# untitled.net
KiCad netlist of a schematic drawn in EAGLE
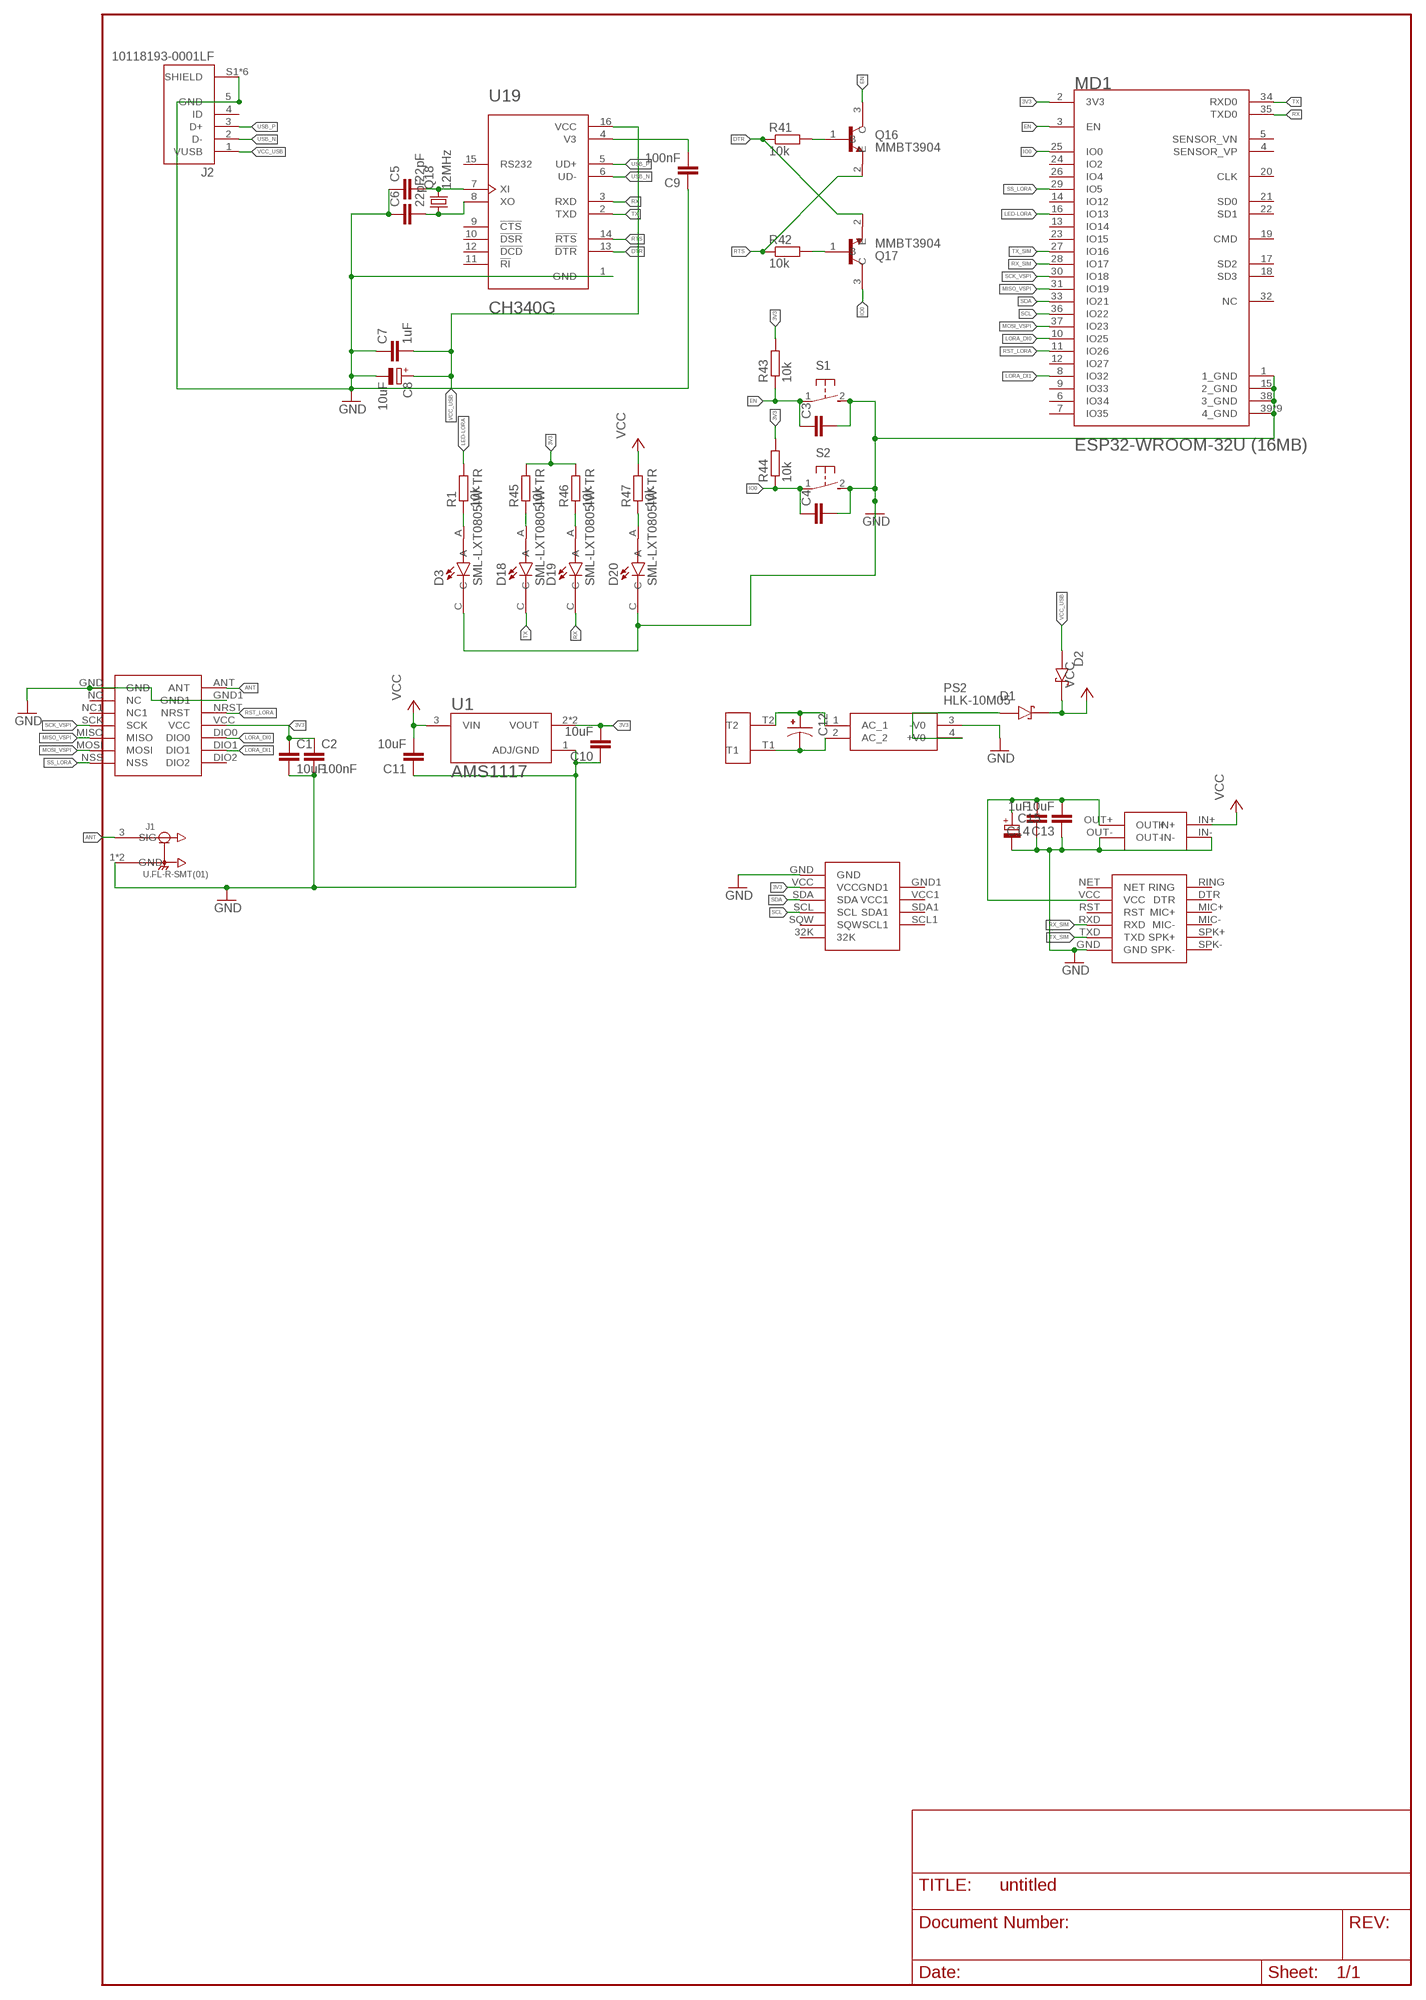
[diagram p0: schematic, sheet 1]

(export (version "E")
  (design (tool "Eeschema 10.0.6"))
  (components
    (comp (ref "C1")
      (value "10uF")
      (footprint "eagle-import:C0805K")
      (libsource (lib "eagle-import") (part "C-EUC0805K"))
    )
    (comp (ref "C2")
      (value "100nF")
      (footprint "eagle-import:C0805K")
      (libsource (lib "eagle-import") (part "C-EUC0805K"))
    )
    (comp (ref "C3")
      (value "C-EUC0805K")
      (footprint "eagle-import:C0805K")
      (libsource (lib "eagle-import") (part "C-EUC0805K"))
    )
    (comp (ref "C4")
      (value "C-EUC0805K")
      (footprint "eagle-import:C0805K")
      (libsource (lib "eagle-import") (part "C-EUC0805K"))
    )
    (comp (ref "C5")
      (value "22pF")
      (footprint "eagle-import:C0805K")
      (libsource (lib "eagle-import") (part "C-EUC0805K"))
    )
    (comp (ref "C6")
      (value "22pF")
      (footprint "eagle-import:C0805K")
      (libsource (lib "eagle-import") (part "C-EUC0805K"))
    )
    (comp (ref "C7")
      (value "1uF")
      (footprint "eagle-import:C0805K")
      (libsource (lib "eagle-import") (part "C-EUC0805K"))
    )
    (comp (ref "C8")
      (value "10uF")
      (footprint "eagle-import:153CLV-0505")
      (libsource (lib "eagle-import") (part "CPOL-EU153CLV-0505"))
    )
    (comp (ref "C9")
      (value "100nF")
      (footprint "eagle-import:C0805K")
      (libsource (lib "eagle-import") (part "C-EUC0805K"))
    )
    (comp (ref "C10")
      (value "10uF")
      (footprint "eagle-import:C0805K")
      (libsource (lib "eagle-import") (part "C-EUC0805K"))
    )
    (comp (ref "C11")
      (value "10uF")
      (footprint "eagle-import:C0805K")
      (libsource (lib "eagle-import") (part "C-EUC0805K"))
    )
    (comp (ref "C12")
      (value "UPM2E100MHD1TO")
      (footprint "eagle-import:CAPPRD500W60D1250H2200")
      (fields (field (name "MF") "Nichicon"))
      (libsource (lib "eagle-import") (part "UPM2E100MHD1TO"))
    )
    (comp (ref "C13")
      (value "10uF")
      (footprint "eagle-import:C0805K")
      (libsource (lib "eagle-import") (part "C-EUC0805K"))
    )
    (comp (ref "C14")
      (value "1uF")
      (footprint "eagle-import:C0805K")
      (libsource (lib "eagle-import") (part "C-EUC0805K"))
    )
    (comp (ref "C15")
      (value "CPOL-EU153CLV-0505")
      (footprint "eagle-import:153CLV-0505")
      (libsource (lib "eagle-import") (part "CPOL-EU153CLV-0505"))
    )
    (comp (ref "D1")
      (value "1N5819HW-7")
      (footprint "eagle-import:SOD3715X145N")
      (fields (field (name "MF") "Diodes Inc."))
      (libsource (lib "eagle-import") (part "1N5819HW-7"))
    )
    (comp (ref "D2")
      (value "1N5819HW-7")
      (footprint "eagle-import:SOD3715X145N")
      (fields (field (name "MF") "Diodes Inc."))
      (libsource (lib "eagle-import") (part "1N5819HW-7"))
    )
    (comp (ref "D3")
      (value "SML-LXT0805IW-TR")
      (footprint "eagle-import:LEDC2012X120N")
      (fields (field (name "MF") "Lumex Opto/Components"))
      (libsource (lib "eagle-import") (part "SML-LXT0805IW-TR"))
    )
    (comp (ref "D18")
      (value "SML-LXT0805IW-TR")
      (footprint "eagle-import:LEDC2012X120N")
      (fields (field (name "MF") "Lumex Opto/Components"))
      (libsource (lib "eagle-import") (part "SML-LXT0805IW-TR"))
    )
    (comp (ref "D19")
      (value "SML-LXT0805IW-TR")
      (footprint "eagle-import:LEDC2012X120N")
      (fields (field (name "MF") "Lumex Opto/Components"))
      (libsource (lib "eagle-import") (part "SML-LXT0805IW-TR"))
    )
    (comp (ref "D20")
      (value "SML-LXT0805IW-TR")
      (footprint "eagle-import:LEDC2012X120N")
      (fields (field (name "MF") "Lumex Opto/Components"))
      (libsource (lib "eagle-import") (part "SML-LXT0805IW-TR"))
    )
    (comp (ref "J1")
      (value "U.FL-R-SMT(01)")
      (footprint "eagle-import:HRS_U.FL-R-SMT(01)")
      (fields (field (name "MF") "Hirose"))
      (libsource (lib "eagle-import") (part "U.FL-R-SMT(01)"))
    )
    (comp (ref "J2")
      (value "10118193-0001LF")
      (footprint "eagle-import:FCI_10118193-0001LF")
      (fields (field (name "MF") "FCI"))
      (libsource (lib "eagle-import") (part "10118193-0001LF"))
    )
    (comp (ref "LORA-NICERF-V1")
      (value "LORA-NICERF-V2")
      (footprint "eagle-import:LORA-NICERF-V2")
      (libsource (lib "eagle-import") (part "LORA-NICERF-V2"))
    )
    (comp (ref "MD1")
      (value "ESPRESSIF_SYSTEMS_ESP32-WROOM-32U_16MBESPRESSIF_SYSTEMS_ESP32-WROOM-32U_16MB_0_0")
      (footprint "eagle-import:ESPRESSIF_SYSTEMS_ESP32-WROOM-32U_16MB_0")
      (fields
        (field (name "DIGIKEY_PART_NUMBER") "1904-1028-1-ND")
        (field (name "MF") "Espressif Systems")
        (field (name "MOUSER_PART_NUMBER") "356-ES32WROOM32U16MB")
      )
      (libsource (lib "eagle-import") (part "ESPRESSIF_SYSTEMS_ESP32-WROOM-32U_16MBESPRESSIF_SYSTEMS_ESP32-WROOM-32U_16MB_0_0"))
    )
    (comp (ref "MINI1")
      (value "MINI360")
      (footprint "eagle-import:MINI360")
      (libsource (lib "eagle-import") (part "MINI360"))
    )
    (comp (ref "PS2")
      (value "HLK-10M05")
      (footprint "eagle-import:HLK10M05")
      (fields (field (name "MF") "Hi-link"))
      (libsource (lib "eagle-import") (part "HLK-10M05"))
    )
    (comp (ref "Q16")
      (value "MMBT3904")
      (footprint "eagle-import:SOT95P240X120-3N")
      (fields (field (name "MF") "ON Semiconductor"))
      (libsource (lib "eagle-import") (part "MMBT3904"))
    )
    (comp (ref "Q17")
      (value "MMBT3904")
      (footprint "eagle-import:SOT95P240X120-3N")
      (fields (field (name "MF") "ON Semiconductor"))
      (libsource (lib "eagle-import") (part "MMBT3904"))
    )
    (comp (ref "Q18")
      (value "12MHz")
      (footprint "eagle-import:SM49")
      (libsource (lib "eagle-import") (part "CRYSTALSM49"))
    )
    (comp (ref "R1")
      (value "10k")
      (footprint "eagle-import:R0805")
      (libsource (lib "eagle-import") (part "R-EU_R0805"))
    )
    (comp (ref "R41")
      (value "10k")
      (footprint "eagle-import:R0805")
      (libsource (lib "eagle-import") (part "R-EU_R0805"))
    )
    (comp (ref "R42")
      (value "10k")
      (footprint "eagle-import:R0805")
      (libsource (lib "eagle-import") (part "R-EU_R0805"))
    )
    (comp (ref "R43")
      (value "10k")
      (footprint "eagle-import:R0805")
      (libsource (lib "eagle-import") (part "R-EU_R0805"))
    )
    (comp (ref "R44")
      (value "10k")
      (footprint "eagle-import:R0805")
      (libsource (lib "eagle-import") (part "R-EU_R0805"))
    )
    (comp (ref "R45")
      (value "10k")
      (footprint "eagle-import:R0805")
      (libsource (lib "eagle-import") (part "R-EU_R0805"))
    )
    (comp (ref "R46")
      (value "10k")
      (footprint "eagle-import:R0805")
      (libsource (lib "eagle-import") (part "R-EU_R0805"))
    )
    (comp (ref "R47")
      (value "10k")
      (footprint "eagle-import:R0805")
      (libsource (lib "eagle-import") (part "R-EU_R0805"))
    )
    (comp (ref "RTC1")
      (value "RTC3231")
      (footprint "eagle-import:RTC3231")
      (libsource (lib "eagle-import") (part "RTC3231"))
    )
    (comp (ref "S1")
      (value "31-XX")
      (footprint "eagle-import:B3F-31XX")
      (fields (field (name "MPN") "B3F-3100"))
      (libsource (lib "eagle-import") (part "31-XX"))
    )
    (comp (ref "S2")
      (value "31-XX")
      (footprint "eagle-import:B3F-31XX")
      (fields (field (name "MPN") "B3F-3100"))
      (libsource (lib "eagle-import") (part "31-XX"))
    )
    (comp (ref "SIM800L1")
      (value "SIM800L")
      (footprint "eagle-import:SIM800L")
      (libsource (lib "eagle-import") (part "SIM800L"))
    )
    (comp (ref "TB7.1")
      (value "TB7.62")
      (footprint "eagle-import:TB7.62")
      (libsource (lib "eagle-import") (part "TB7.62"))
    )
    (comp (ref "U1")
      (value "AMS1117")
      (footprint "eagle-import:SOT229P700X180-4N")
      (fields (field (name "MF") "Advanced Monolithic Systems"))
      (libsource (lib "eagle-import") (part "AMS1117"))
    )
    (comp (ref "U19")
      (value "CH340G")
      (footprint "eagle-import:SOIC127P600X180-16N")
      (fields (field (name "MF") "WCH") (field (name "MP") "Ch340G"))
      (libsource (lib "eagle-import") (part "CH340G"))
    )
  )
  (nets
    (net (code "1") (name "3V3") (class "Default")
      (node (ref "C1") (pin "1") (pinfunction "1_1") (pintype "passive"))
      (node (ref "C10") (pin "2") (pinfunction "2_2") (pintype "passive"))
      (node (ref "C2") (pin "1") (pinfunction "1_1") (pintype "passive"))
      (node (ref "LORA-NICERF-V1") (pin "VCC") (pinfunction "VCC_VCC") (pintype "bidirectional"))
      (node (ref "MD1") (pin "2") (pinfunction "3V3_2") (pintype "power_in"))
      (node (ref "R43") (pin "2") (pinfunction "2_2") (pintype "passive"))
      (node (ref "R44") (pin "2") (pinfunction "2_2") (pintype "passive"))
      (node (ref "R45") (pin "2") (pinfunction "2_2") (pintype "passive"))
      (node (ref "R46") (pin "2") (pinfunction "2_2") (pintype "passive"))
      (node (ref "RTC1") (pin "VCC") (pinfunction "VCC_VCC") (pintype "bidirectional"))
      (node (ref "U1") (pin "2") (pinfunction "VOUT_2") (pintype "output"))
      (node (ref "U1") (pin "4") (pinfunction "VOUT_4") (pintype "output"))
    )
    (net (code "2") (name "ANT") (class "Default")
      (node (ref "J1") (pin "3") (pinfunction "SIG_3") (pintype "passive"))
      (node (ref "LORA-NICERF-V1") (pin "ANT") (pinfunction "ANT_ANT") (pintype "bidirectional"))
    )
    (net (code "3") (name "DTR") (class "Default")
      (node (ref "Q17") (pin "2") (pinfunction "E_2") (pintype "passive"))
      (node (ref "R41") (pin "1") (pinfunction "1_1") (pintype "passive"))
      (node (ref "U19") (pin "13") (pinfunction "~{DTR}_13") (pintype "output"))
    )
    (net (code "4") (name "EN") (class "Default")
      (node (ref "C3") (pin "1") (pinfunction "1_1") (pintype "passive"))
      (node (ref "MD1") (pin "3") (pinfunction "EN_3") (pintype "input"))
      (node (ref "Q16") (pin "3") (pinfunction "C_3") (pintype "passive"))
      (node (ref "R43") (pin "1") (pinfunction "1_1") (pintype "passive"))
      (node (ref "S1") (pin "1") (pinfunction "P_1") (pintype "passive"))
    )
    (net (code "5") (name "GND") (class "Default")
      (node (ref "C1") (pin "2") (pinfunction "2_2") (pintype "passive"))
      (node (ref "C10") (pin "1") (pinfunction "1_1") (pintype "passive"))
      (node (ref "C11") (pin "1") (pinfunction "1_1") (pintype "passive"))
      (node (ref "C13") (pin "1") (pinfunction "1_1") (pintype "passive"))
      (node (ref "C14") (pin "1") (pinfunction "1_1") (pintype "passive"))
      (node (ref "C15") (pin "-") (pinfunction "-_-") (pintype "passive"))
      (node (ref "C2") (pin "2") (pinfunction "2_2") (pintype "passive"))
      (node (ref "C3") (pin "2") (pinfunction "2_2") (pintype "passive"))
      (node (ref "C4") (pin "2") (pinfunction "2_2") (pintype "passive"))
      (node (ref "C5") (pin "1") (pinfunction "1_1") (pintype "passive"))
      (node (ref "C6") (pin "1") (pinfunction "1_1") (pintype "passive"))
      (node (ref "C7") (pin "1") (pinfunction "1_1") (pintype "passive"))
      (node (ref "C8") (pin "-") (pinfunction "-_-") (pintype "passive"))
      (node (ref "C9") (pin "1") (pinfunction "1_1") (pintype "passive"))
      (node (ref "D20") (pin "C") (pinfunction "C_C") (pintype "passive"))
      (node (ref "D3") (pin "C") (pinfunction "C_C") (pintype "passive"))
      (node (ref "J1") (pin "1") (pinfunction "GND_1") (pintype "passive"))
      (node (ref "J1") (pin "2") (pinfunction "GND_2") (pintype "passive"))
      (node (ref "J2") (pin "5") (pinfunction "GND_5") (pintype "passive"))
      (node (ref "J2") (pin "S1") (pinfunction "SHIELD_S1") (pintype "passive"))
      (node (ref "J2") (pin "S2") (pinfunction "SHIELD_S2") (pintype "passive"))
      (node (ref "J2") (pin "S3") (pinfunction "SHIELD_S3") (pintype "passive"))
      (node (ref "J2") (pin "S4") (pinfunction "SHIELD_S4") (pintype "passive"))
      (node (ref "J2") (pin "S5") (pinfunction "SHIELD_S5") (pintype "passive"))
      (node (ref "J2") (pin "S6") (pinfunction "SHIELD_S6") (pintype "passive"))
      (node (ref "LORA-NICERF-V1") (pin "GND") (pinfunction "GND_GND") (pintype "bidirectional"))
      (node (ref "LORA-NICERF-V1") (pin "GND1") (pinfunction "GND1_GND1") (pintype "bidirectional"))
      (node (ref "MD1") (pin "1") (pinfunction "1_GND_1") (pintype "power_in"))
      (node (ref "MD1") (pin "15") (pinfunction "2_GND_15") (pintype "power_in"))
      (node (ref "MD1") (pin "38") (pinfunction "3_GND_38") (pintype "power_in"))
      (node (ref "MD1") (pin "39") (pinfunction "4_GND_39") (pintype "power_in"))
      (node (ref "MD1") (pin "39-2") (pinfunction "4_GND_39-2") (pintype "power_in"))
      (node (ref "MD1") (pin "39-3") (pinfunction "4_GND_39-3") (pintype "power_in"))
      (node (ref "MD1") (pin "39-4") (pinfunction "4_GND_39-4") (pintype "power_in"))
      (node (ref "MD1") (pin "39-5") (pinfunction "4_GND_39-5") (pintype "power_in"))
      (node (ref "MD1") (pin "39-6") (pinfunction "4_GND_39-6") (pintype "power_in"))
      (node (ref "MD1") (pin "39-7") (pinfunction "4_GND_39-7") (pintype "power_in"))
      (node (ref "MD1") (pin "39-8") (pinfunction "4_GND_39-8") (pintype "power_in"))
      (node (ref "MD1") (pin "39-9") (pinfunction "4_GND_39-9") (pintype "power_in"))
      (node (ref "MINI1") (pin "IN-") (pinfunction "IN-_IN-") (pintype "bidirectional"))
      (node (ref "MINI1") (pin "OUT-") (pinfunction "OUT-_OUT-") (pintype "bidirectional"))
      (node (ref "PS2") (pin "3") (pinfunction "-V0_3") (pintype "bidirectional"))
      (node (ref "RTC1") (pin "GND") (pinfunction "GND_GND") (pintype "bidirectional"))
      (node (ref "S1") (pin "2") (pinfunction "S_2") (pintype "passive"))
      (node (ref "S2") (pin "2") (pinfunction "S_2") (pintype "passive"))
      (node (ref "SIM800L1") (pin "GND") (pinfunction "GND_GND") (pintype "bidirectional"))
      (node (ref "U1") (pin "1") (pinfunction "ADJ/GND_1") (pintype "power_in"))
      (node (ref "U19") (pin "1") (pinfunction "GND_1") (pintype "power_in"))
    )
    (net (code "6") (name "IO0") (class "Default")
      (node (ref "C4") (pin "1") (pinfunction "1_1") (pintype "passive"))
      (node (ref "MD1") (pin "25") (pinfunction "IO0_25") (pintype "bidirectional"))
      (node (ref "Q17") (pin "3") (pinfunction "C_3") (pintype "passive"))
      (node (ref "R44") (pin "1") (pinfunction "1_1") (pintype "passive"))
      (node (ref "S2") (pin "1") (pinfunction "P_1") (pintype "passive"))
    )
    (net (code "7") (name "LED-LORA") (class "Default")
      (node (ref "MD1") (pin "16") (pinfunction "IO13_16") (pintype "bidirectional"))
      (node (ref "R1") (pin "2") (pinfunction "2_2") (pintype "passive"))
    )
    (net (code "8") (name "LORA_DI0") (class "Default")
      (node (ref "LORA-NICERF-V1") (pin "DIO0") (pinfunction "DIO0_DIO0") (pintype "bidirectional"))
      (node (ref "MD1") (pin "10") (pinfunction "IO25_10") (pintype "bidirectional"))
    )
    (net (code "9") (name "LORA_DI1") (class "Default")
      (node (ref "LORA-NICERF-V1") (pin "DIO1") (pinfunction "DIO1_DIO1") (pintype "bidirectional"))
      (node (ref "MD1") (pin "8") (pinfunction "IO32_8") (pintype "bidirectional"))
    )
    (net (code "10") (name "MISO_VSPI") (class "Default")
      (node (ref "LORA-NICERF-V1") (pin "MISO") (pinfunction "MISO_MISO") (pintype "bidirectional"))
      (node (ref "MD1") (pin "31") (pinfunction "IO19_31") (pintype "bidirectional"))
    )
    (net (code "11") (name "MOSI_VSPI") (class "Default")
      (node (ref "LORA-NICERF-V1") (pin "MOSI") (pinfunction "MOSI_MOSI") (pintype "bidirectional"))
      (node (ref "MD1") (pin "37") (pinfunction "IO23_37") (pintype "bidirectional"))
    )
    (net (code "12") (name "Net-(C13-Pad2)") (class "Default")
      (node (ref "C13") (pin "2") (pinfunction "2_2") (pintype "passive"))
      (node (ref "C14") (pin "2") (pinfunction "2_2") (pintype "passive"))
      (node (ref "C15") (pin "+") (pinfunction "+_+") (pintype "passive"))
      (node (ref "MINI1") (pin "OUT+") (pinfunction "OUT+_OUT+") (pintype "bidirectional"))
      (node (ref "SIM800L1") (pin "VCC") (pinfunction "VCC_VCC") (pintype "bidirectional"))
    )
    (net (code "13") (name "Net-(D3-PadA)") (class "Default")
      (node (ref "D3") (pin "A") (pinfunction "A_A") (pintype "passive"))
      (node (ref "R1") (pin "1") (pinfunction "1_1") (pintype "passive"))
    )
    (net (code "14") (name "Net-(D18-PadA)") (class "Default")
      (node (ref "D18") (pin "A") (pinfunction "A_A") (pintype "passive"))
      (node (ref "R45") (pin "1") (pinfunction "1_1") (pintype "passive"))
    )
    (net (code "15") (name "Net-(D19-PadA)") (class "Default")
      (node (ref "D19") (pin "A") (pinfunction "A_A") (pintype "passive"))
      (node (ref "R46") (pin "1") (pinfunction "1_1") (pintype "passive"))
    )
    (net (code "16") (name "Net-(D20-PadA)") (class "Default")
      (node (ref "D20") (pin "A") (pinfunction "A_A") (pintype "passive"))
      (node (ref "R47") (pin "1") (pinfunction "1_1") (pintype "passive"))
    )
    (net (code "17") (name "Net-(PS2-+V0)") (class "Default")
      (node (ref "D1") (pin "A") (pinfunction "A_A") (pintype "passive"))
      (node (ref "PS2") (pin "4") (pinfunction "+V0_4") (pintype "bidirectional"))
    )
    (net (code "18") (name "Net-(PS2-AC_1)") (class "Default")
      (node (ref "C12") (pin "P") (pinfunction "P_P") (pintype "passive"))
      (node (ref "PS2") (pin "1") (pinfunction "AC_1_1") (pintype "bidirectional"))
      (node (ref "TB7.1") (pin "T2") (pinfunction "T2_T2") (pintype "bidirectional"))
    )
    (net (code "19") (name "Net-(PS2-AC_2)") (class "Default")
      (node (ref "C12") (pin "N") (pinfunction "N_N") (pintype "passive"))
      (node (ref "PS2") (pin "2") (pinfunction "AC_2_2") (pintype "bidirectional"))
      (node (ref "TB7.1") (pin "T1") (pinfunction "T1_T1") (pintype "bidirectional"))
    )
    (net (code "20") (name "Net-(Q16-B)") (class "Default")
      (node (ref "Q16") (pin "1") (pinfunction "B_1") (pintype "passive"))
      (node (ref "R41") (pin "2") (pinfunction "2_2") (pintype "passive"))
    )
    (net (code "21") (name "Net-(Q17-B)") (class "Default")
      (node (ref "Q17") (pin "1") (pinfunction "B_1") (pintype "passive"))
      (node (ref "R42") (pin "2") (pinfunction "2_2") (pintype "passive"))
    )
    (net (code "22") (name "Net-(U19-V3)") (class "Default")
      (node (ref "C9") (pin "2") (pinfunction "2_2") (pintype "passive"))
      (node (ref "U19") (pin "4") (pinfunction "V3_4") (pintype "power_in"))
    )
    (net (code "23") (name "Net-(U19-XI)") (class "Default")
      (node (ref "C5") (pin "2") (pinfunction "2_2") (pintype "passive"))
      (node (ref "Q18") (pin "2") (pinfunction "2_2") (pintype "passive"))
      (node (ref "U19") (pin "7") (pinfunction "XI_7") (pintype "input"))
    )
    (net (code "24") (name "Net-(U19-XO)") (class "Default")
      (node (ref "C6") (pin "2") (pinfunction "2_2") (pintype "passive"))
      (node (ref "Q18") (pin "1") (pinfunction "1_1") (pintype "passive"))
      (node (ref "U19") (pin "8") (pinfunction "XO_8") (pintype "output"))
    )
    (net (code "25") (name "RST_LORA") (class "Default")
      (node (ref "LORA-NICERF-V1") (pin "NRST") (pinfunction "NRST_NRST") (pintype "bidirectional"))
      (node (ref "MD1") (pin "11") (pinfunction "IO26_11") (pintype "bidirectional"))
    )
    (net (code "26") (name "RTS") (class "Default")
      (node (ref "Q16") (pin "2") (pinfunction "E_2") (pintype "passive"))
      (node (ref "R42") (pin "1") (pinfunction "1_1") (pintype "passive"))
      (node (ref "U19") (pin "14") (pinfunction "~{RTS}_14") (pintype "output"))
    )
    (net (code "27") (name "RX") (class "Default")
      (node (ref "D19") (pin "C") (pinfunction "C_C") (pintype "passive"))
      (node (ref "MD1") (pin "35") (pinfunction "TXD0_35") (pintype "bidirectional"))
      (node (ref "U19") (pin "3") (pinfunction "RXD_3") (pintype "input"))
    )
    (net (code "28") (name "RX_SIM") (class "Default")
      (node (ref "MD1") (pin "28") (pinfunction "IO17_28") (pintype "bidirectional"))
      (node (ref "SIM800L1") (pin "RXD") (pinfunction "RXD_RXD") (pintype "bidirectional"))
    )
    (net (code "29") (name "SCK_VSPI") (class "Default")
      (node (ref "LORA-NICERF-V1") (pin "SCK") (pinfunction "SCK_SCK") (pintype "bidirectional"))
      (node (ref "MD1") (pin "30") (pinfunction "IO18_30") (pintype "bidirectional"))
    )
    (net (code "30") (name "SCL") (class "Default")
      (node (ref "MD1") (pin "36") (pinfunction "IO22_36") (pintype "bidirectional"))
      (node (ref "RTC1") (pin "SCL") (pinfunction "SCL_SCL") (pintype "bidirectional"))
    )
    (net (code "31") (name "SDA") (class "Default")
      (node (ref "MD1") (pin "33") (pinfunction "IO21_33") (pintype "bidirectional"))
      (node (ref "RTC1") (pin "SDA") (pinfunction "SDA_SDA") (pintype "bidirectional"))
    )
    (net (code "32") (name "SS_LORA") (class "Default")
      (node (ref "LORA-NICERF-V1") (pin "NSS") (pinfunction "NSS_NSS") (pintype "bidirectional"))
      (node (ref "MD1") (pin "29") (pinfunction "IO5_29") (pintype "bidirectional"))
    )
    (net (code "33") (name "TX") (class "Default")
      (node (ref "D18") (pin "C") (pinfunction "C_C") (pintype "passive"))
      (node (ref "MD1") (pin "34") (pinfunction "RXD0_34") (pintype "bidirectional"))
      (node (ref "U19") (pin "2") (pinfunction "TXD_2") (pintype "output"))
    )
    (net (code "34") (name "TX_SIM") (class "Default")
      (node (ref "MD1") (pin "27") (pinfunction "IO16_27") (pintype "bidirectional"))
      (node (ref "SIM800L1") (pin "TXD") (pinfunction "TXD_TXD") (pintype "bidirectional"))
    )
    (net (code "35") (name "USB_N") (class "Default")
      (node (ref "J2") (pin "2") (pinfunction "D-_2") (pintype "passive"))
      (node (ref "U19") (pin "6") (pinfunction "UD-_6") (pintype "bidirectional"))
    )
    (net (code "36") (name "USB_P") (class "Default")
      (node (ref "J2") (pin "3") (pinfunction "D+_3") (pintype "passive"))
      (node (ref "U19") (pin "5") (pinfunction "UD+_5") (pintype "bidirectional"))
    )
    (net (code "37") (name "VCC") (class "Default")
      (node (ref "C11") (pin "2") (pinfunction "2_2") (pintype "passive"))
      (node (ref "D1") (pin "C") (pinfunction "K_C") (pintype "passive"))
      (node (ref "D2") (pin "C") (pinfunction "K_C") (pintype "passive"))
      (node (ref "MINI1") (pin "IN+") (pinfunction "IN+_IN+") (pintype "bidirectional"))
      (node (ref "R47") (pin "2") (pinfunction "2_2") (pintype "passive"))
      (node (ref "U1") (pin "3") (pinfunction "VIN_3") (pintype "input"))
    )
    (net (code "38") (name "VCC_USB") (class "Default")
      (node (ref "C7") (pin "2") (pinfunction "2_2") (pintype "passive"))
      (node (ref "C8") (pin "+") (pinfunction "+_+") (pintype "passive"))
      (node (ref "D2") (pin "A") (pinfunction "A_A") (pintype "passive"))
      (node (ref "J2") (pin "1") (pinfunction "VUSB_1") (pintype "passive"))
      (node (ref "U19") (pin "16") (pinfunction "VCC_16") (pintype "power_in"))
    )
    (net (code "39") (name "unconnected-(J2-ID-Pad4)") (class "Default")
      (node (ref "J2") (pin "4") (pinfunction "ID_4") (pintype "passive"))
    )
    (net (code "40") (name "unconnected-(LORA-NICERF-V1-PadDIO2)") (class "Default")
      (node (ref "LORA-NICERF-V1") (pin "DIO2") (pinfunction "DIO2_DIO2") (pintype "bidirectional"))
    )
    (net (code "41") (name "unconnected-(LORA-NICERF-V1-PadNC)") (class "Default")
      (node (ref "LORA-NICERF-V1") (pin "NC") (pinfunction "NC_NC") (pintype "bidirectional"))
    )
    (net (code "42") (name "unconnected-(LORA-NICERF-V1-PadNC1)") (class "Default")
      (node (ref "LORA-NICERF-V1") (pin "NC1") (pinfunction "NC1_NC1") (pintype "bidirectional"))
    )
    (net (code "43") (name "unconnected-(MD1-CLK-Pad20)") (class "Default")
      (node (ref "MD1") (pin "20") (pinfunction "CLK_20") (pintype "bidirectional"))
    )
    (net (code "44") (name "unconnected-(MD1-CMD-Pad19)") (class "Default")
      (node (ref "MD1") (pin "19") (pinfunction "CMD_19") (pintype "bidirectional"))
    )
    (net (code "45") (name "unconnected-(MD1-IO2-Pad24)") (class "Default")
      (node (ref "MD1") (pin "24") (pinfunction "IO2_24") (pintype "bidirectional"))
    )
    (net (code "46") (name "unconnected-(MD1-IO4-Pad26)") (class "Default")
      (node (ref "MD1") (pin "26") (pinfunction "IO4_26") (pintype "bidirectional"))
    )
    (net (code "47") (name "unconnected-(MD1-IO12-Pad14)") (class "Default")
      (node (ref "MD1") (pin "14") (pinfunction "IO12_14") (pintype "bidirectional"))
    )
    (net (code "48") (name "unconnected-(MD1-IO14-Pad13)") (class "Default")
      (node (ref "MD1") (pin "13") (pinfunction "IO14_13") (pintype "bidirectional"))
    )
    (net (code "49") (name "unconnected-(MD1-IO15-Pad23)") (class "Default")
      (node (ref "MD1") (pin "23") (pinfunction "IO15_23") (pintype "bidirectional"))
    )
    (net (code "50") (name "unconnected-(MD1-IO27-Pad12)") (class "Default")
      (node (ref "MD1") (pin "12") (pinfunction "IO27_12") (pintype "bidirectional"))
    )
    (net (code "51") (name "unconnected-(MD1-IO33-Pad9)") (class "Default")
      (node (ref "MD1") (pin "9") (pinfunction "IO33_9") (pintype "bidirectional"))
    )
    (net (code "52") (name "unconnected-(MD1-IO34-Pad6)") (class "Default")
      (node (ref "MD1") (pin "6") (pinfunction "IO34_6") (pintype "bidirectional"))
    )
    (net (code "53") (name "unconnected-(MD1-IO35-Pad7)") (class "Default")
      (node (ref "MD1") (pin "7") (pinfunction "IO35_7") (pintype "bidirectional"))
    )
    (net (code "54") (name "unconnected-(MD1-NC-Pad32)") (class "Default")
      (node (ref "MD1") (pin "32") (pinfunction "NC_32") (pintype "passive"))
    )
    (net (code "55") (name "unconnected-(MD1-SD0-Pad21)") (class "Default")
      (node (ref "MD1") (pin "21") (pinfunction "SD0_21") (pintype "bidirectional"))
    )
    (net (code "56") (name "unconnected-(MD1-SD1-Pad22)") (class "Default")
      (node (ref "MD1") (pin "22") (pinfunction "SD1_22") (pintype "bidirectional"))
    )
    (net (code "57") (name "unconnected-(MD1-SD2-Pad17)") (class "Default")
      (node (ref "MD1") (pin "17") (pinfunction "SD2_17") (pintype "bidirectional"))
    )
    (net (code "58") (name "unconnected-(MD1-SD3-Pad18)") (class "Default")
      (node (ref "MD1") (pin "18") (pinfunction "SD3_18") (pintype "bidirectional"))
    )
    (net (code "59") (name "unconnected-(MD1-SENSOR_VN-Pad5)") (class "Default")
      (node (ref "MD1") (pin "5") (pinfunction "SENSOR_VN_5") (pintype "input"))
    )
    (net (code "60") (name "unconnected-(MD1-SENSOR_VP-Pad4)") (class "Default")
      (node (ref "MD1") (pin "4") (pinfunction "SENSOR_VP_4") (pintype "input"))
    )
    (net (code "61") (name "unconnected-(RTC1-Pad32K)") (class "Default")
      (node (ref "RTC1") (pin "32K") (pinfunction "32K_32K") (pintype "bidirectional"))
    )
    (net (code "62") (name "unconnected-(RTC1-PadGND1)") (class "Default")
      (node (ref "RTC1") (pin "GND1") (pinfunction "GND1_GND1") (pintype "bidirectional"))
    )
    (net (code "63") (name "unconnected-(RTC1-PadSCL1)") (class "Default")
      (node (ref "RTC1") (pin "SCL1") (pinfunction "SCL1_SCL1") (pintype "bidirectional"))
    )
    (net (code "64") (name "unconnected-(RTC1-PadSDA1)") (class "Default")
      (node (ref "RTC1") (pin "SDA1") (pinfunction "SDA1_SDA1") (pintype "bidirectional"))
    )
    (net (code "65") (name "unconnected-(RTC1-PadSQW)") (class "Default")
      (node (ref "RTC1") (pin "SQW") (pinfunction "SQW_SQW") (pintype "bidirectional"))
    )
    (net (code "66") (name "unconnected-(RTC1-PadVCC1)") (class "Default")
      (node (ref "RTC1") (pin "VCC1") (pinfunction "VCC1_VCC1") (pintype "bidirectional"))
    )
    (net (code "67") (name "unconnected-(SIM800L1-PadDTR)") (class "Default")
      (node (ref "SIM800L1") (pin "DTR") (pinfunction "DTR_DTR") (pintype "bidirectional"))
    )
    (net (code "68") (name "unconnected-(SIM800L1-PadMIC+)") (class "Default")
      (node (ref "SIM800L1") (pin "MIC+") (pinfunction "MIC+_MIC+") (pintype "bidirectional"))
    )
    (net (code "69") (name "unconnected-(SIM800L1-PadMIC-)") (class "Default")
      (node (ref "SIM800L1") (pin "MIC-") (pinfunction "MIC-_MIC-") (pintype "bidirectional"))
    )
    (net (code "70") (name "unconnected-(SIM800L1-PadNET)") (class "Default")
      (node (ref "SIM800L1") (pin "NET") (pinfunction "NET_NET") (pintype "bidirectional"))
    )
    (net (code "71") (name "unconnected-(SIM800L1-PadRING)") (class "Default")
      (node (ref "SIM800L1") (pin "RING") (pinfunction "RING_RING") (pintype "bidirectional"))
    )
    (net (code "72") (name "unconnected-(SIM800L1-PadRST)") (class "Default")
      (node (ref "SIM800L1") (pin "RST") (pinfunction "RST_RST") (pintype "bidirectional"))
    )
    (net (code "73") (name "unconnected-(SIM800L1-PadSPK+)") (class "Default")
      (node (ref "SIM800L1") (pin "SPK+") (pinfunction "SPK+_SPK+") (pintype "bidirectional"))
    )
    (net (code "74") (name "unconnected-(SIM800L1-PadSPK-)") (class "Default")
      (node (ref "SIM800L1") (pin "SPK-") (pinfunction "SPK-_SPK-") (pintype "bidirectional"))
    )
    (net (code "75") (name "unconnected-(U19-RS232-Pad15)") (class "Default")
      (node (ref "U19") (pin "15") (pinfunction "RS232_15") (pintype "input"))
    )
    (net (code "76") (name "unconnected-(U19-~{CTS}-Pad9)") (class "Default")
      (node (ref "U19") (pin "9") (pinfunction "~{CTS}_9") (pintype "input"))
    )
    (net (code "77") (name "unconnected-(U19-~{DCD}-Pad12)") (class "Default")
      (node (ref "U19") (pin "12") (pinfunction "~{DCD}_12") (pintype "input"))
    )
    (net (code "78") (name "unconnected-(U19-~{DSR}-Pad10)") (class "Default")
      (node (ref "U19") (pin "10") (pinfunction "~{DSR}_10") (pintype "input"))
    )
    (net (code "79") (name "unconnected-(U19-~{RI}-Pad11)") (class "Default")
      (node (ref "U19") (pin "11") (pinfunction "~{RI}_11") (pintype "input"))
    )
  )
)
